# FRONT-UNIT-3_5.net
KiCad netlist of a schematic drawn in Altium Designer
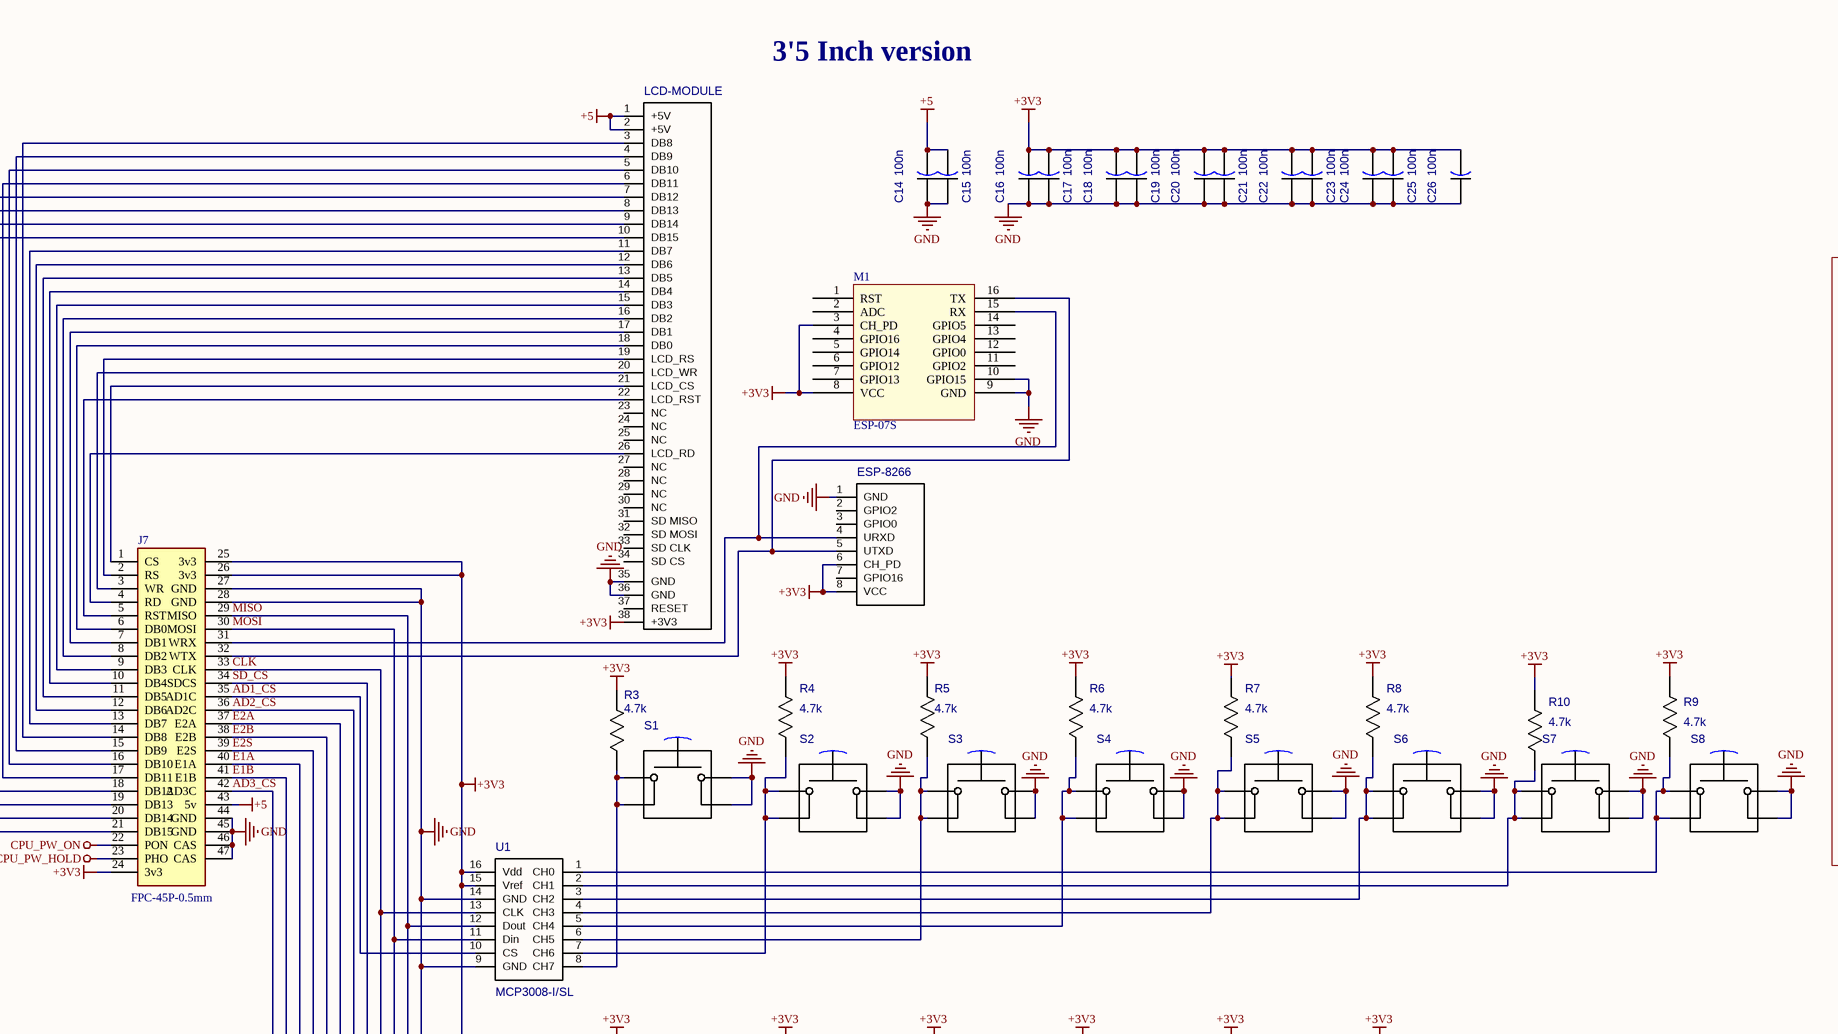
[diagram p0: FRONT-UNIT-3.5.SCHDOC, top left]
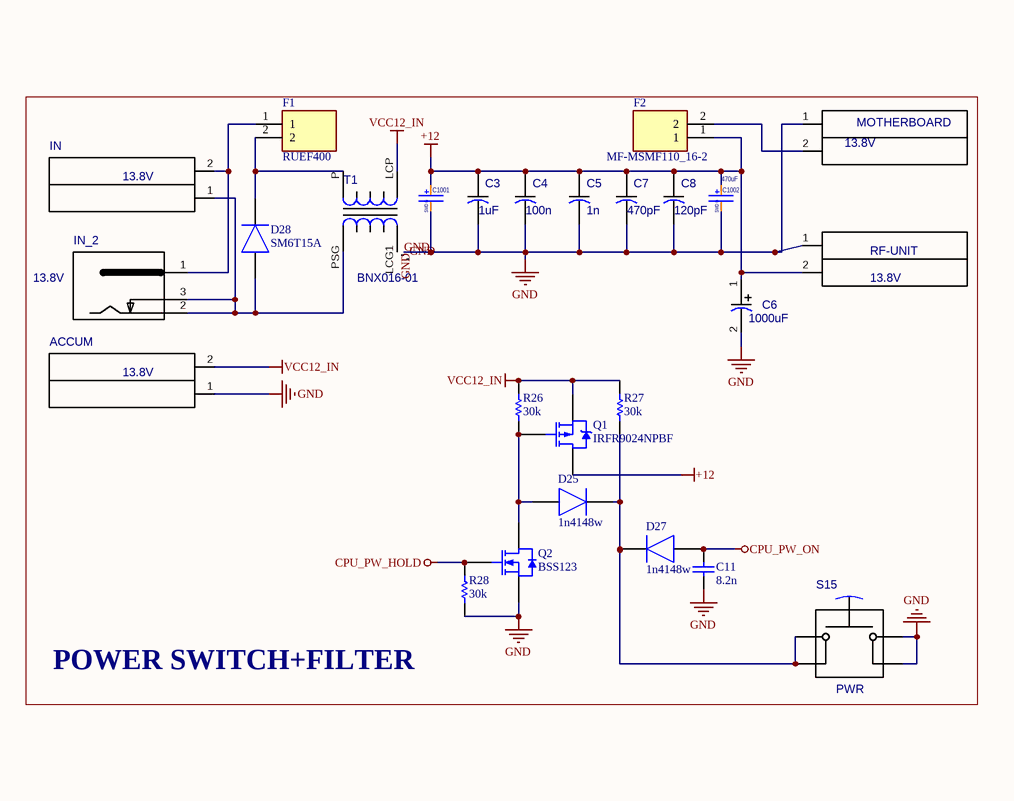
[diagram p1: FRONT-UNIT-3.5.SCHDOC, top right]
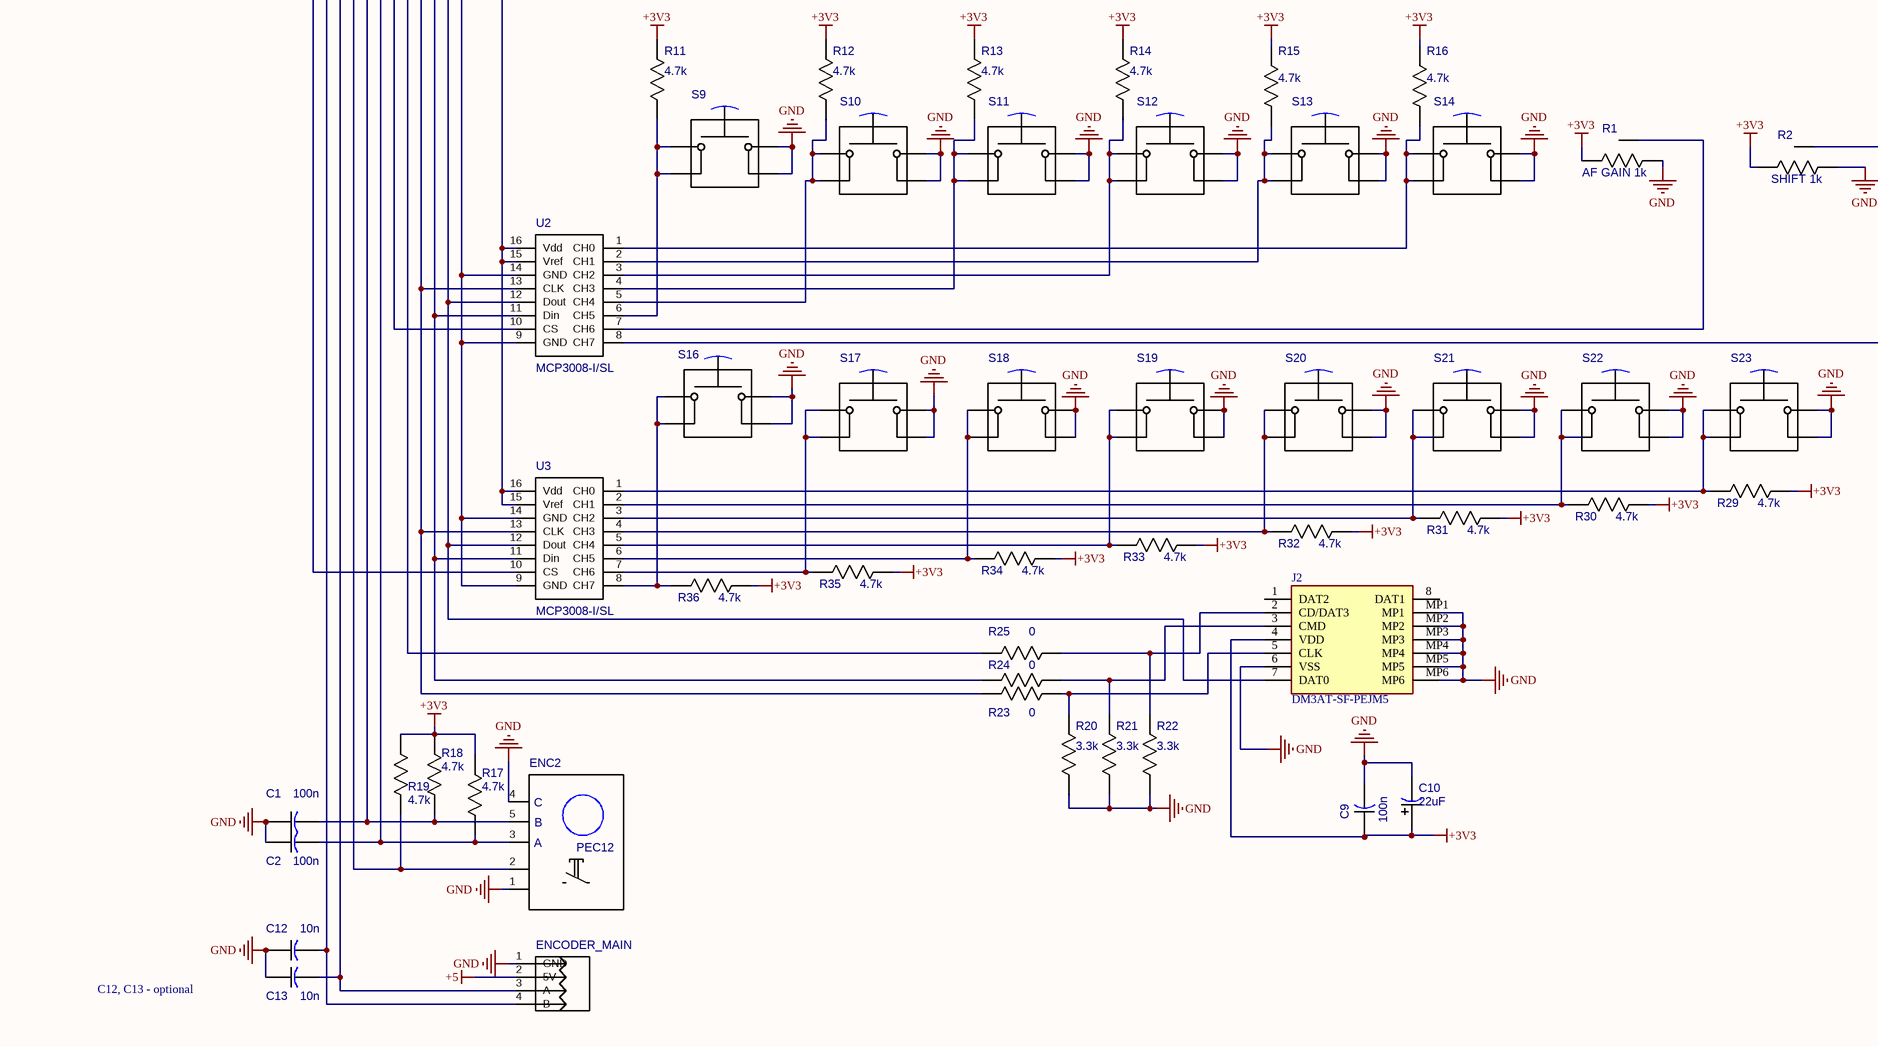
[diagram p2: FRONT-UNIT-3.5.SCHDOC, bottom left]
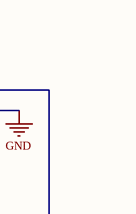
[diagram p3: FRONT-UNIT-3.5.SCHDOC, bottom right]

(export (version "E")
  (design (tool "Eeschema 10.0.6"))
  (components
    (comp (ref "ACCUM")
      (value "13.8V")
      (footprint "JX2")
      (description "JX2")
      (libsource (lib "*") (part "JX2"))
    )
    (comp (ref "C1")
      (value "100n")
      (footprint "CAP_0805")
      (description "CAP_0805")
      (libsource (lib "*") (part "CAP_0805"))
    )
    (comp (ref "C2")
      (value "100n")
      (footprint "CAP_0805")
      (description "CAP_0805")
      (libsource (lib "*") (part "CAP_0805"))
    )
    (comp (ref "C3")
      (value "1uF")
      (footprint "CAP_1206")
      (description "CAP_1206")
      (libsource (lib "*") (part "CAP_1206"))
    )
    (comp (ref "C4")
      (value "100n")
      (footprint "CAP_1206")
      (description "CAP_1206")
      (libsource (lib "*") (part "CAP_1206"))
    )
    (comp (ref "C5")
      (value "1n")
      (footprint "CAP_1206")
      (description "CAP_1206")
      (libsource (lib "*") (part "CAP_1206"))
    )
    (comp (ref "C6")
      (value "1000uF")
      (footprint "CAP250RP")
      (description "CAP250RP")
      (libsource (lib "FRONT-UNIT-3.5") (part "CAP250RP"))
    )
    (comp (ref "C7")
      (value "470pF")
      (footprint "CAP_1206")
      (description "CAP_1206")
      (libsource (lib "*") (part "CAP_1206"))
    )
    (comp (ref "C8")
      (value "120pF")
      (footprint "CAP_1206")
      (description "CAP_1206")
      (libsource (lib "*") (part "CAP_1206"))
    )
    (comp (ref "C9")
      (value "100n")
      (footprint "CAP_0805")
      (description "CAP_0805")
      (libsource (lib "*") (part "CAP_0805"))
    )
    (comp (ref "C10")
      (value "22uF")
      (footprint "EEEFC_sizeB")
      (description "EEEFC_sizeB")
      (libsource (lib "*") (part "EEEFC_sizeB"))
    )
    (comp (ref "C11")
      (value "8.2n")
      (footprint "CAPC2013X94X50LL20T25")
      (description "CAP_1206")
      (fields
        (field (name "MANUFACTURER") "AVX Interconnect / Elco")
        (field (name "PART NUMBER") "08055C822KAT2A")
      )
      (libsource (lib "Altium Content Vault") (part "CAP"))
    )
    (comp (ref "C12")
      (value "10n")
      (footprint "CAP_0805")
      (description "CAP_0805")
      (libsource (lib "*") (part "CAP_0805"))
    )
    (comp (ref "C13")
      (value "10n")
      (footprint "CAP_0805")
      (description "CAP_0805")
      (libsource (lib "*") (part "CAP_0805"))
    )
    (comp (ref "C14")
      (value "100n")
      (footprint "CAP_0805")
      (description "CAP_0805")
      (libsource (lib "*") (part "CAP_0805"))
    )
    (comp (ref "C15")
      (value "100n")
      (footprint "CAP_0805")
      (description "CAP_0805")
      (libsource (lib "*") (part "CAP_0805"))
    )
    (comp (ref "C16")
      (value "100n")
      (footprint "CAP_0805")
      (description "CAP_0805")
      (libsource (lib "*") (part "CAP_0805"))
    )
    (comp (ref "C17")
      (value "100n")
      (footprint "CAP_0805")
      (description "CAP_0805")
      (libsource (lib "*") (part "CAP_0805"))
    )
    (comp (ref "C18")
      (value "100n")
      (footprint "CAP_0805")
      (description "CAP_0805")
      (libsource (lib "*") (part "CAP_0805"))
    )
    (comp (ref "C19")
      (value "100n")
      (footprint "CAP_0805")
      (description "CAP_0805")
      (libsource (lib "*") (part "CAP_0805"))
    )
    (comp (ref "C20")
      (value "100n")
      (footprint "CAP_0805")
      (description "CAP_0805")
      (libsource (lib "*") (part "CAP_0805"))
    )
    (comp (ref "C21")
      (value "100n")
      (footprint "CAP_0805")
      (description "CAP_0805")
      (libsource (lib "*") (part "CAP_0805"))
    )
    (comp (ref "C22")
      (value "100n")
      (footprint "CAP_0805")
      (description "CAP_0805")
      (libsource (lib "*") (part "CAP_0805"))
    )
    (comp (ref "C23")
      (value "100n")
      (footprint "CAP_0805")
      (description "CAP_0805")
      (libsource (lib "*") (part "CAP_0805"))
    )
    (comp (ref "C24")
      (value "100n")
      (footprint "CAP_0805")
      (description "CAP_0805")
      (libsource (lib "*") (part "CAP_0805"))
    )
    (comp (ref "C25")
      (value "100n")
      (footprint "CAP_0805")
      (description "CAP_0805")
      (libsource (lib "*") (part "CAP_0805"))
    )
    (comp (ref "C26")
      (value "100n")
      (footprint "CAP_0805")
      (description "CAP_0805")
      (libsource (lib "*") (part "CAP_0805"))
    )
    (comp (ref "C1001")
      (value "470uF")
      (footprint "SMD-G-10X10.2")
      (description "10x7.7, 8.7, 10, 10.5, 12.5")
      (fields (field (name "PUBLISHER") "Catcatcat Electronics"))
      (libsource (lib "CapacitorElectrolytic") (part "_SMD-G-10"))
    )
    (comp (ref "C1002")
      (value "470uF")
      (footprint "SMD-G-10X10.2")
      (description "10x7.7, 8.7, 10, 10.5, 12.5")
      (fields (field (name "PUBLISHER") "Catcatcat Electronics"))
      (libsource (lib "CapacitorElectrolytic") (part "_SMD-G-10"))
    )
    (comp (ref "D25")
      (value "1n4148w")
      (footprint "SamacSys:SOD3716X135N")
      (description "Diode")
      (libsource (lib "*") (part "1n4148w"))
    )
    (comp (ref "D27")
      (value "1n4148w")
      (footprint "SamacSys:SOD3716X135N")
      (description "Diode")
      (libsource (lib "*") (part "1n4148w"))
    )
    (comp (ref "D28")
      (value "SM6T15A")
      (footprint "SamacSys:SMBJ36CATR")
      (description "Diode")
      (fields (field (name "MOUSER PART NUMBER") "511-SM6T15A") (field (name "RS PART NUMBER") "4864915P"))
      (libsource (lib "*") (part "SM6T15A"))
    )
    (comp (ref "ENC2") (value "PEC12") (footprint "PEC12") (libsource (lib "*") (part "PEC12")))
    (comp (ref "ENCODER_MAIN")
      (value "OPTICAL ENCODER")
      (footprint "644456-4")
      (libsource (lib "*") (part "644456-4"))
    )
    (comp (ref "ESP-8266")
      (value "ESP-01 ESP8266")
      (footprint "ESP-01 ESP8266")
      (libsource (lib "FRONT-UNIT") (part "ESP-01 ESP8266"))
    )
    (comp (ref "F1")
      (value "RUEF400")
      (footprint "SamacSys:RUEF400")
      (description "Fuse")
      (fields (field (name "MOUSER PART NUMBER") "650-RUEF400") (field (name "RS PART NUMBER") "5176837P"))
      (libsource (lib "*") (part "RUEF400"))
    )
    (comp (ref "F2")
      (value "MF-MSMF110_16-2")
      (footprint "SamacSys:FUSC4632X85N")
      (description "Fuse")
      (fields
        (field (name "MANUFACTURER_PART_NUMBER") "MF-MSMF110/16-2")
        (field (name "MOUSER PART NUMBER") "652-MF-MSMF110/16-2")
      )
      (libsource (lib "*") (part "MF-MSMF110_16-2"))
    )
    (comp (ref "IN") (value "13.8V") (footprint "JX2") (description "JX2") (libsource (lib "*") (part "JX2")))
    (comp (ref "IN_2")
      (value "13.8V")
      (footprint "PJ-050B")
      (description "PJ-050B")
      (libsource (lib "*") (part "PJ-050B"))
    )
    (comp (ref "J2")
      (value "DM3AT-SF-PEJM5")
      (footprint "FRONT-UNIT-71:DM3ATSFPEJM5")
      (description "Connector")
      (libsource (lib "FRONT-UNIT-71") (part "DM3AT-SF-PEJM5"))
    )
    (comp (ref "J7")
      (value "FPC-45P-0.5mm")
      (footprint "FRONT-UNIT-3.5:FH12S45S05SH60")
      (description "Connector")
      (fields
        (field (name "MANUFACTURER_PART_NUMBER") "FH12S-45S-0.5SH(55)")
        (field (name "MOUSER PART NUMBER") "798-FH12S-45S-05SH55")
      )
      (libsource (lib "*") (part "FH12S-45S-0.5SH_55_"))
    )
    (comp (ref "LCD-MODULE")
      (value "~")
      (footprint "LCD-MODULE-3.2-480-320")
      (description "LCD-MODULE_3'2_480х320")
      (libsource (lib "FRONT-UNIT-3.5") (part "LCD-MODULE_3'2_480х320"))
    )
    (comp (ref "M1")
      (value "ESP-07S")
      (footprint "modules:ESP-07S")
      (libsource (lib "modules") (part "ESP-07S"))
    )
    (comp (ref "MOTHERBOARD")
      (value "13.8V")
      (footprint "JX2")
      (description "JX2")
      (libsource (lib "*") (part "JX2"))
    )
    (comp (ref "Q1")
      (value "IRFR9024NPBF")
      (footprint "ONSC-DPAK-3-369C-01_V")
      (description "IRFR9024NPBF, Транзистор, Р-канал 55В 11А")
      (fields (field (name "MANUFACTURER") "On Semiconductor") (field (name "PARTNUMBER") "NTD2955G"))
      (libsource (lib "Altium Content Vault") (part "ONSC-PMOS-G1S3D4-3_B"))
    )
    (comp (ref "Q2")
      (value "BSS123")
      (footprint "FAIR-SOT23-3_V")
      (fields (field (name "MANUFACTURER") "Fairchild"))
      (libsource (lib "Altium Content Vault") (part "NEMOS-GSD-3"))
    )
    (comp (ref "R1")
      (value "AF GAIN 1k")
      (footprint "PTV09")
      (description "Adjustable Resistor PTV09")
      (fields (field (name "Comment") "ptv09a-4225f-b102"))
      (libsource (lib "*") (part "PTV09"))
    )
    (comp (ref "R2")
      (value "SHIFT 1k")
      (footprint "PTV09")
      (description "Adjustable Resistor PTV09")
      (fields (field (name "Comment") "ptv09a-4225f-b102"))
      (libsource (lib "*") (part "PTV09"))
    )
    (comp (ref "R3")
      (value "4.7k")
      (footprint "RES_0805")
      (description "RES_0805")
      (libsource (lib "*") (part "RES_0805"))
    )
    (comp (ref "R4")
      (value "4.7k")
      (footprint "RES_0805")
      (description "RES_0805")
      (libsource (lib "*") (part "RES_0805"))
    )
    (comp (ref "R5")
      (value "4.7k")
      (footprint "RES_0805")
      (description "RES_0805")
      (libsource (lib "*") (part "RES_0805"))
    )
    (comp (ref "R6")
      (value "4.7k")
      (footprint "RES_0805")
      (description "RES_0805")
      (libsource (lib "*") (part "RES_0805"))
    )
    (comp (ref "R7")
      (value "4.7k")
      (footprint "RES_0805")
      (description "RES_0805")
      (libsource (lib "*") (part "RES_0805"))
    )
    (comp (ref "R8")
      (value "4.7k")
      (footprint "RES_0805")
      (description "RES_0805")
      (libsource (lib "*") (part "RES_0805"))
    )
    (comp (ref "R9")
      (value "4.7k")
      (footprint "RES_0805")
      (description "RES_0805")
      (libsource (lib "*") (part "RES_0805"))
    )
    (comp (ref "R10")
      (value "4.7k")
      (footprint "RES_0805")
      (description "RES_0805")
      (libsource (lib "*") (part "RES_0805"))
    )
    (comp (ref "R11")
      (value "4.7k")
      (footprint "RES_0805")
      (description "RES_0805")
      (libsource (lib "*") (part "RES_0805"))
    )
    (comp (ref "R12")
      (value "4.7k")
      (footprint "RES_0805")
      (description "RES_0805")
      (libsource (lib "*") (part "RES_0805"))
    )
    (comp (ref "R13")
      (value "4.7k")
      (footprint "RES_0805")
      (description "RES_0805")
      (libsource (lib "*") (part "RES_0805"))
    )
    (comp (ref "R14")
      (value "4.7k")
      (footprint "RES_0805")
      (description "RES_0805")
      (libsource (lib "*") (part "RES_0805"))
    )
    (comp (ref "R15")
      (value "4.7k")
      (footprint "RES_0805")
      (description "RES_0805")
      (libsource (lib "*") (part "RES_0805"))
    )
    (comp (ref "R16")
      (value "4.7k")
      (footprint "RES_0805")
      (description "RES_0805")
      (libsource (lib "*") (part "RES_0805"))
    )
    (comp (ref "R17")
      (value "4.7k")
      (footprint "RES_0805")
      (description "RES_0805")
      (libsource (lib "*") (part "RES_0805"))
    )
    (comp (ref "R18")
      (value "4.7k")
      (footprint "RES_0805")
      (description "RES_0805")
      (libsource (lib "*") (part "RES_0805"))
    )
    (comp (ref "R19")
      (value "4.7k")
      (footprint "RES_0805")
      (description "RES_0805")
      (libsource (lib "*") (part "RES_0805"))
    )
    (comp (ref "R20")
      (value "3.3k")
      (footprint "RES_0805")
      (description "RES_0805")
      (libsource (lib "*") (part "RES_0805"))
    )
    (comp (ref "R21")
      (value "3.3k")
      (footprint "RES_0805")
      (description "RES_0805")
      (libsource (lib "*") (part "RES_0805"))
    )
    (comp (ref "R22")
      (value "3.3k")
      (footprint "RES_0805")
      (description "RES_0805")
      (libsource (lib "*") (part "RES_0805"))
    )
    (comp (ref "R23")
      (value "0")
      (footprint "RES_0805")
      (description "RES_0805")
      (libsource (lib "*") (part "RES_0805"))
    )
    (comp (ref "R24")
      (value "0")
      (footprint "RES_0805")
      (description "RES_0805")
      (libsource (lib "*") (part "RES_0805"))
    )
    (comp (ref "R25")
      (value "0")
      (footprint "RES_0805")
      (description "RES_0805")
      (libsource (lib "*") (part "RES_0805"))
    )
    (comp (ref "R26")
      (value "30k")
      (footprint "RESC2013X60X40NL20T25")
      (description "RES_0805")
      (fields (field (name "MANUFACTURER") "Panasonic") (field (name "PART NUMBER") "ERA-6AEB303V"))
      (libsource (lib "Altium Content Vault") (part "RES"))
    )
    (comp (ref "R27")
      (value "30k")
      (footprint "RESC2013X60X40NL20T25")
      (description "RES_0805")
      (fields (field (name "MANUFACTURER") "Panasonic") (field (name "PART NUMBER") "ERA-6AEB303V"))
      (libsource (lib "Altium Content Vault") (part "RES"))
    )
    (comp (ref "R28")
      (value "30k")
      (footprint "RESC2013X60X40NL20T25")
      (description "RES_0805")
      (fields (field (name "MANUFACTURER") "Panasonic") (field (name "PART NUMBER") "ERA-6AEB303V"))
      (libsource (lib "Altium Content Vault") (part "RES"))
    )
    (comp (ref "R29")
      (value "4.7k")
      (footprint "RES_0805")
      (description "RES_0805")
      (libsource (lib "*") (part "RES_0805"))
    )
    (comp (ref "R30")
      (value "4.7k")
      (footprint "RES_0805")
      (description "RES_0805")
      (libsource (lib "*") (part "RES_0805"))
    )
    (comp (ref "R31")
      (value "4.7k")
      (footprint "RES_0805")
      (description "RES_0805")
      (libsource (lib "*") (part "RES_0805"))
    )
    (comp (ref "R32")
      (value "4.7k")
      (footprint "RES_0805")
      (description "RES_0805")
      (libsource (lib "*") (part "RES_0805"))
    )
    (comp (ref "R33")
      (value "4.7k")
      (footprint "RES_0805")
      (description "RES_0805")
      (libsource (lib "*") (part "RES_0805"))
    )
    (comp (ref "R34")
      (value "4.7k")
      (footprint "RES_0805")
      (description "RES_0805")
      (libsource (lib "*") (part "RES_0805"))
    )
    (comp (ref "R35")
      (value "4.7k")
      (footprint "RES_0805")
      (description "RES_0805")
      (libsource (lib "*") (part "RES_0805"))
    )
    (comp (ref "R36")
      (value "4.7k")
      (footprint "RES_0805")
      (description "RES_0805")
      (libsource (lib "*") (part "RES_0805"))
    )
    (comp (ref "RF-UNIT")
      (value "13.8V")
      (footprint "JX2")
      (description "JX2")
      (libsource (lib "*") (part "JX2"))
    )
    (comp (ref "S1")
      (value "PTS645SK50LFS")
      (footprint "PTS645SK50LFS")
      (fields (field (name "LCSC PART #") "test"))
      (libsource (lib "*") (part "PTS645SK50LFS"))
    )
    (comp (ref "S2")
      (value "PTS645SK50LFS")
      (footprint "PTS645SK50LFS")
      (libsource (lib "*") (part "PTS645SK50LFS"))
    )
    (comp (ref "S3")
      (value "PTS645SK50LFS")
      (footprint "PTS645SK50LFS")
      (libsource (lib "*") (part "PTS645SK50LFS"))
    )
    (comp (ref "S4")
      (value "PTS645SK50LFS")
      (footprint "PTS645SK50LFS")
      (libsource (lib "*") (part "PTS645SK50LFS"))
    )
    (comp (ref "S5")
      (value "PTS645SK50LFS")
      (footprint "PTS645SK50LFS")
      (libsource (lib "*") (part "PTS645SK50LFS"))
    )
    (comp (ref "S6")
      (value "PTS645SK50LFS")
      (footprint "PTS645SK50LFS")
      (libsource (lib "*") (part "PTS645SK50LFS"))
    )
    (comp (ref "S7")
      (value "PTS645SK50LFS")
      (footprint "PTS645SK50LFS")
      (libsource (lib "*") (part "PTS645SK50LFS"))
    )
    (comp (ref "S8")
      (value "PTS645SK50LFS")
      (footprint "PTS645SK50LFS")
      (libsource (lib "*") (part "PTS645SK50LFS"))
    )
    (comp (ref "S9")
      (value "PTS645SK50LFS")
      (footprint "PTS645SK50LFS")
      (libsource (lib "*") (part "PTS645SK50LFS"))
    )
    (comp (ref "S10")
      (value "PTS645SK50LFS")
      (footprint "PTS645SK50LFS")
      (libsource (lib "*") (part "PTS645SK50LFS"))
    )
    (comp (ref "S11")
      (value "PTS645SK50LFS")
      (footprint "PTS645SK50LFS")
      (libsource (lib "*") (part "PTS645SK50LFS"))
    )
    (comp (ref "S12")
      (value "PTS645SK50LFS")
      (footprint "PTS645SK50LFS")
      (libsource (lib "*") (part "PTS645SK50LFS"))
    )
    (comp (ref "S13")
      (value "PTS645SK50LFS")
      (footprint "PTS645SK50LFS")
      (libsource (lib "*") (part "PTS645SK50LFS"))
    )
    (comp (ref "S14")
      (value "PTS645SK50LFS")
      (footprint "PTS645SK50LFS")
      (libsource (lib "*") (part "PTS645SK50LFS"))
    )
    (comp (ref "S15")
      (value "PWR")
      (footprint "PTS645SK50LFS")
      (description "PTS645SK50LFS")
      (libsource (lib "*") (part "PTS645SK50LFS"))
    )
    (comp (ref "S16")
      (value "PTS645SK50LFS")
      (footprint "PTS645SK50LFS")
      (libsource (lib "*") (part "PTS645SK50LFS"))
    )
    (comp (ref "S17")
      (value "PTS645SK50LFS")
      (footprint "PTS645SK50LFS")
      (libsource (lib "*") (part "PTS645SK50LFS"))
    )
    (comp (ref "S18")
      (value "PTS645SK50LFS")
      (footprint "PTS645SK50LFS")
      (libsource (lib "*") (part "PTS645SK50LFS"))
    )
    (comp (ref "S19")
      (value "PTS645SK50LFS")
      (footprint "PTS645SK50LFS")
      (libsource (lib "*") (part "PTS645SK50LFS"))
    )
    (comp (ref "S20")
      (value "PTS645SK50LFS")
      (footprint "PTS645SK50LFS")
      (libsource (lib "*") (part "PTS645SK50LFS"))
    )
    (comp (ref "S21")
      (value "PTS645SK50LFS")
      (footprint "PTS645SK50LFS")
      (libsource (lib "*") (part "PTS645SK50LFS"))
    )
    (comp (ref "S22")
      (value "PTS645SK50LFS")
      (footprint "PTS645SK50LFS")
      (libsource (lib "*") (part "PTS645SK50LFS"))
    )
    (comp (ref "S23")
      (value "PTS645SK50LFS")
      (footprint "PTS645SK50LFS")
      (libsource (lib "*") (part "PTS645SK50LFS"))
    )
    (comp (ref "T1")
      (value "BNX016-01")
      (footprint "TRANSF_ICORE")
      (libsource (lib "*") (part "TRANSF_ICORE"))
    )
    (comp (ref "U1")
      (value "MCP3008-I/SL")
      (footprint "MCP3008-I/SL")
      (libsource (lib "*") (part "MCP3008-I/SL"))
    )
    (comp (ref "U2")
      (value "MCP3008-I/SL")
      (footprint "MCP3008-I/SL")
      (libsource (lib "*") (part "MCP3008-I/SL"))
    )
    (comp (ref "U3")
      (value "MCP3008-I/SL")
      (footprint "MCP3008-I/SL")
      (libsource (lib "*") (part "MCP3008-I/SL"))
    )
  )
  (nets
    (net (code "1") (name "+3V3") (class "Default")
      (node (ref "C10") (pin "1") (pinfunction "PLUS_1") (pintype "passive"))
      (node (ref "C16") (pin "2") (pinfunction "2_2") (pintype "passive"))
      (node (ref "C17") (pin "2") (pinfunction "2_2") (pintype "passive"))
      (node (ref "C18") (pin "2") (pinfunction "2_2") (pintype "passive"))
      (node (ref "C19") (pin "2") (pinfunction "2_2") (pintype "passive"))
      (node (ref "C20") (pin "2") (pinfunction "2_2") (pintype "passive"))
      (node (ref "C21") (pin "2") (pinfunction "2_2") (pintype "passive"))
      (node (ref "C22") (pin "2") (pinfunction "2_2") (pintype "passive"))
      (node (ref "C23") (pin "2") (pinfunction "2_2") (pintype "passive"))
      (node (ref "C24") (pin "2") (pinfunction "2_2") (pintype "passive"))
      (node (ref "C25") (pin "2") (pinfunction "2_2") (pintype "passive"))
      (node (ref "C26") (pin "2") (pinfunction "2_2") (pintype "passive"))
      (node (ref "C9") (pin "1") (pinfunction "1_1") (pintype "passive"))
      (node (ref "ESP-8266") (pin "6") (pinfunction "CH_PD_6") (pintype "passive"))
      (node (ref "ESP-8266") (pin "8") (pinfunction "VCC_8") (pintype "passive"))
      (node (ref "J2") (pin "4") (pinfunction "VDD_4") (pintype "passive"))
      (node (ref "J7") (pin "24") (pinfunction "3v3_24") (pintype "passive"))
      (node (ref "J7") (pin "25") (pinfunction "3v3_25") (pintype "passive"))
      (node (ref "J7") (pin "26") (pinfunction "3v3_26") (pintype "passive"))
      (node (ref "LCD-MODULE") (pin "38") (pinfunction "+3V3_38") (pintype "passive"))
      (node (ref "M1") (pin "3") (pinfunction "CH_PD_3") (pintype "passive"))
      (node (ref "M1") (pin "8") (pinfunction "VCC_8") (pintype "passive"))
      (node (ref "R1") (pin "1") (pinfunction "CW_1") (pintype "passive"))
      (node (ref "R10") (pin "2") (pinfunction "2_2") (pintype "passive"))
      (node (ref "R11") (pin "2") (pinfunction "2_2") (pintype "passive"))
      (node (ref "R12") (pin "2") (pinfunction "2_2") (pintype "passive"))
      (node (ref "R13") (pin "2") (pinfunction "2_2") (pintype "passive"))
      (node (ref "R14") (pin "2") (pinfunction "2_2") (pintype "passive"))
      (node (ref "R15") (pin "2") (pinfunction "2_2") (pintype "passive"))
      (node (ref "R16") (pin "2") (pinfunction "2_2") (pintype "passive"))
      (node (ref "R17") (pin "2") (pinfunction "2_2") (pintype "passive"))
      (node (ref "R18") (pin "2") (pinfunction "2_2") (pintype "passive"))
      (node (ref "R19") (pin "2") (pinfunction "2_2") (pintype "passive"))
      (node (ref "R2") (pin "1") (pinfunction "CW_1") (pintype "passive"))
      (node (ref "R29") (pin "2") (pinfunction "2_2") (pintype "passive"))
      (node (ref "R3") (pin "2") (pinfunction "2_2") (pintype "passive"))
      (node (ref "R30") (pin "2") (pinfunction "2_2") (pintype "passive"))
      (node (ref "R31") (pin "2") (pinfunction "2_2") (pintype "passive"))
      (node (ref "R32") (pin "2") (pinfunction "2_2") (pintype "passive"))
      (node (ref "R33") (pin "2") (pinfunction "2_2") (pintype "passive"))
      (node (ref "R34") (pin "2") (pinfunction "2_2") (pintype "passive"))
      (node (ref "R35") (pin "2") (pinfunction "2_2") (pintype "passive"))
      (node (ref "R36") (pin "2") (pinfunction "2_2") (pintype "passive"))
      (node (ref "R4") (pin "2") (pinfunction "2_2") (pintype "passive"))
      (node (ref "R5") (pin "2") (pinfunction "2_2") (pintype "passive"))
      (node (ref "R6") (pin "2") (pinfunction "2_2") (pintype "passive"))
      (node (ref "R7") (pin "2") (pinfunction "2_2") (pintype "passive"))
      (node (ref "R8") (pin "2") (pinfunction "2_2") (pintype "passive"))
      (node (ref "R9") (pin "2") (pinfunction "2_2") (pintype "passive"))
      (node (ref "U1") (pin "15") (pinfunction "Vref_15") (pintype "passive"))
      (node (ref "U1") (pin "16") (pinfunction "Vdd_16") (pintype "passive"))
      (node (ref "U2") (pin "15") (pinfunction "Vref_15") (pintype "passive"))
      (node (ref "U2") (pin "16") (pinfunction "Vdd_16") (pintype "passive"))
      (node (ref "U3") (pin "15") (pinfunction "Vref_15") (pintype "passive"))
      (node (ref "U3") (pin "16") (pinfunction "Vdd_16") (pintype "passive"))
    )
    (net (code "2") (name "+5") (class "Default")
      (node (ref "C14") (pin "2") (pinfunction "2_2") (pintype "passive"))
      (node (ref "C15") (pin "2") (pinfunction "2_2") (pintype "passive"))
      (node (ref "ENCODER_MAIN") (pin "2") (pinfunction "5V_2") (pintype "passive"))
      (node (ref "J7") (pin "43") (pinfunction "5v_43") (pintype "passive"))
      (node (ref "LCD-MODULE") (pin "1") (pinfunction "+5V_1") (pintype "passive"))
      (node (ref "LCD-MODULE") (pin "2") (pinfunction "+5V_2") (pintype "passive"))
    )
    (net (code "3") (name "+12") (class "Default")
      (node (ref "C1001") (pin "1") (pinfunction "1_1") (pintype "passive"))
      (node (ref "C1002") (pin "1") (pinfunction "1_1") (pintype "passive"))
      (node (ref "C3") (pin "1") (pinfunction "1_1") (pintype "passive"))
      (node (ref "C4") (pin "1") (pinfunction "1_1") (pintype "passive"))
      (node (ref "C5") (pin "1") (pinfunction "1_1") (pintype "passive"))
      (node (ref "C6") (pin "1") (pinfunction "PLUS_1") (pintype "passive"))
      (node (ref "C7") (pin "1") (pinfunction "1_1") (pintype "passive"))
      (node (ref "C8") (pin "1") (pinfunction "1_1") (pintype "passive"))
      (node (ref "F2") (pin "1") (pinfunction "1_1") (pintype "passive"))
      (node (ref "Q1") (pin "4") (pinfunction "D_4") (pintype "passive"))
      (node (ref "RF-UNIT") (pin "2") (pinfunction "1_2") (pintype "passive"))
    )
    (net (code "4") (name "/AD1_CS") (class "Default")
      (node (ref "J7") (pin "35") (pinfunction "AD1C_35") (pintype "passive"))
      (node (ref "U1") (pin "10") (pinfunction "CS_10") (pintype "passive"))
    )
    (net (code "5") (name "/AD2_CS") (class "Default")
      (node (ref "J7") (pin "36") (pinfunction "AD2C_36") (pintype "passive"))
      (node (ref "U2") (pin "10") (pinfunction "CS_10") (pintype "passive"))
    )
    (net (code "6") (name "/AD3_CS") (class "Default")
      (node (ref "J7") (pin "42") (pinfunction "AD3C_42") (pintype "passive"))
      (node (ref "U3") (pin "10") (pinfunction "CS_10") (pintype "passive"))
    )
    (net (code "7") (name "/CLK") (class "Default")
      (node (ref "J7") (pin "33") (pinfunction "CLK_33") (pintype "passive"))
      (node (ref "R23") (pin "2") (pinfunction "2_2") (pintype "passive"))
      (node (ref "U1") (pin "13") (pinfunction "CLK_13") (pintype "passive"))
      (node (ref "U2") (pin "13") (pinfunction "CLK_13") (pintype "passive"))
      (node (ref "U3") (pin "13") (pinfunction "CLK_13") (pintype "passive"))
    )
    (net (code "8") (name "/E1A") (class "Default")
      (node (ref "C13") (pin "2") (pinfunction "2_2") (pintype "passive"))
      (node (ref "ENCODER_MAIN") (pin "3") (pinfunction "A_3") (pintype "passive"))
      (node (ref "J7") (pin "40") (pinfunction "E1A_40") (pintype "passive"))
    )
    (net (code "9") (name "/E1B") (class "Default")
      (node (ref "C12") (pin "2") (pinfunction "2_2") (pintype "passive"))
      (node (ref "ENCODER_MAIN") (pin "4") (pinfunction "B_4") (pintype "passive"))
      (node (ref "J7") (pin "41") (pinfunction "E1B_41") (pintype "passive"))
    )
    (net (code "10") (name "/E2A") (class "Default")
      (node (ref "C2") (pin "2") (pinfunction "2_2") (pintype "passive"))
      (node (ref "ENC2") (pin "3") (pinfunction "A_3") (pintype "passive"))
      (node (ref "J7") (pin "37") (pinfunction "E2A_37") (pintype "passive"))
      (node (ref "R17") (pin "1") (pinfunction "1_1") (pintype "passive"))
    )
    (net (code "11") (name "/E2B") (class "Default")
      (node (ref "C1") (pin "2") (pinfunction "2_2") (pintype "passive"))
      (node (ref "ENC2") (pin "5") (pinfunction "B_5") (pintype "passive"))
      (node (ref "J7") (pin "38") (pinfunction "E2B_38") (pintype "passive"))
      (node (ref "R18") (pin "1") (pinfunction "1_1") (pintype "passive"))
    )
    (net (code "12") (name "/E2S") (class "Default")
      (node (ref "ENC2") (pin "2") (pinfunction "2_2") (pintype "passive"))
      (node (ref "J7") (pin "39") (pinfunction "E2S_39") (pintype "passive"))
      (node (ref "R19") (pin "1") (pinfunction "1_1") (pintype "passive"))
    )
    (net (code "13") (name "/MISO") (class "Default")
      (node (ref "J2") (pin "7") (pinfunction "DAT0_7") (pintype "passive"))
      (node (ref "J7") (pin "29") (pinfunction "MISO_29") (pintype "passive"))
      (node (ref "U1") (pin "12") (pinfunction "Dout_12") (pintype "passive"))
      (node (ref "U2") (pin "12") (pinfunction "Dout_12") (pintype "passive"))
      (node (ref "U3") (pin "12") (pinfunction "Dout_12") (pintype "passive"))
    )
    (net (code "14") (name "/MOSI") (class "Default")
      (node (ref "J7") (pin "30") (pinfunction "MOSI_30") (pintype "passive"))
      (node (ref "R24") (pin "2") (pinfunction "2_2") (pintype "passive"))
      (node (ref "U1") (pin "11") (pinfunction "Din_11") (pintype "passive"))
      (node (ref "U2") (pin "11") (pinfunction "Din_11") (pintype "passive"))
      (node (ref "U3") (pin "11") (pinfunction "Din_11") (pintype "passive"))
    )
    (net (code "15") (name "/SD_CS") (class "Default")
      (node (ref "J7") (pin "34") (pinfunction "SDCS_34") (pintype "passive"))
      (node (ref "R25") (pin "2") (pinfunction "2_2") (pintype "passive"))
    )
    (net (code "16") (name "CPU_PW_HOLD") (class "Default")
      (node (ref "J7") (pin "23") (pinfunction "PHO_23") (pintype "passive"))
      (node (ref "Q2") (pin "1") (pinfunction "G_1") (pintype "passive"))
      (node (ref "R28") (pin "2") (pinfunction "2_2") (pintype "passive"))
    )
    (net (code "17") (name "CPU_PW_ON") (class "Default")
      (node (ref "C11") (pin "2") (pinfunction "2_2") (pintype "passive"))
      (node (ref "D27") (pin "2") (pinfunction "A_2") (pintype "passive"))
      (node (ref "J7") (pin "22") (pinfunction "PON_22") (pintype "passive"))
    )
    (net (code "18") (name "GND") (class "Default")
      (node (ref "ACCUM") (pin "1") (pinfunction "2_1") (pintype "passive"))
      (node (ref "C1") (pin "1") (pinfunction "1_1") (pintype "passive"))
      (node (ref "C10") (pin "2") (pinfunction "MINUS_2") (pintype "passive"))
      (node (ref "C1001") (pin "2") (pinfunction "2_2") (pintype "passive"))
      (node (ref "C1002") (pin "2") (pinfunction "2_2") (pintype "passive"))
      (node (ref "C11") (pin "1") (pinfunction "1_1") (pintype "passive"))
      (node (ref "C12") (pin "1") (pinfunction "1_1") (pintype "passive"))
      (node (ref "C13") (pin "1") (pinfunction "1_1") (pintype "passive"))
      (node (ref "C14") (pin "1") (pinfunction "1_1") (pintype "passive"))
      (node (ref "C15") (pin "1") (pinfunction "1_1") (pintype "passive"))
      (node (ref "C16") (pin "1") (pinfunction "1_1") (pintype "passive"))
      (node (ref "C17") (pin "1") (pinfunction "1_1") (pintype "passive"))
      (node (ref "C18") (pin "1") (pinfunction "1_1") (pintype "passive"))
      (node (ref "C19") (pin "1") (pinfunction "1_1") (pintype "passive"))
      (node (ref "C2") (pin "1") (pinfunction "1_1") (pintype "passive"))
      (node (ref "C20") (pin "1") (pinfunction "1_1") (pintype "passive"))
      (node (ref "C21") (pin "1") (pinfunction "1_1") (pintype "passive"))
      (node (ref "C22") (pin "1") (pinfunction "1_1") (pintype "passive"))
      (node (ref "C23") (pin "1") (pinfunction "1_1") (pintype "passive"))
      (node (ref "C24") (pin "1") (pinfunction "1_1") (pintype "passive"))
      (node (ref "C25") (pin "1") (pinfunction "1_1") (pintype "passive"))
      (node (ref "C26") (pin "1") (pinfunction "1_1") (pintype "passive"))
      (node (ref "C3") (pin "2") (pinfunction "2_2") (pintype "passive"))
      (node (ref "C4") (pin "2") (pinfunction "2_2") (pintype "passive"))
      (node (ref "C5") (pin "2") (pinfunction "2_2") (pintype "passive"))
      (node (ref "C6") (pin "2") (pinfunction "MINUS_2") (pintype "passive"))
      (node (ref "C7") (pin "2") (pinfunction "2_2") (pintype "passive"))
      (node (ref "C8") (pin "2") (pinfunction "2_2") (pintype "passive"))
      (node (ref "C9") (pin "2") (pinfunction "2_2") (pintype "passive"))
      (node (ref "ENC2") (pin "1") (pinfunction "1_1") (pintype "passive"))
      (node (ref "ENC2") (pin "4") (pinfunction "C_4") (pintype "passive"))
      (node (ref "ENCODER_MAIN") (pin "1") (pinfunction "GND_1") (pintype "passive"))
      (node (ref "ESP-8266") (pin "1") (pinfunction "GND_1") (pintype "passive"))
      (node (ref "J2") (pin "6") (pinfunction "VSS_6") (pintype "passive"))
      (node (ref "J2") (pin "MP1") (pinfunction "MP1_MP1") (pintype "passive"))
      (node (ref "J2") (pin "MP2") (pinfunction "MP2_MP2") (pintype "passive"))
      (node (ref "J2") (pin "MP3") (pinfunction "MP3_MP3") (pintype "passive"))
      (node (ref "J2") (pin "MP4") (pinfunction "MP4_MP4") (pintype "passive"))
      (node (ref "J2") (pin "MP5") (pinfunction "MP5_MP5") (pintype "passive"))
      (node (ref "J2") (pin "MP6") (pinfunction "MP6_MP6") (pintype "passive"))
      (node (ref "J7") (pin "27") (pinfunction "GND_27") (pintype "passive"))
      (node (ref "J7") (pin "28") (pinfunction "GND_28") (pintype "passive"))
      (node (ref "J7") (pin "44") (pinfunction "GND_44") (pintype "passive"))
      (node (ref "J7") (pin "45") (pinfunction "GND_45") (pintype "passive"))
      (node (ref "J7") (pin "46") (pinfunction "CAS_46") (pintype "passive"))
      (node (ref "J7") (pin "47") (pinfunction "CAS_47") (pintype "passive"))
      (node (ref "LCD-MODULE") (pin "35") (pinfunction "GND_35") (pintype "passive"))
      (node (ref "LCD-MODULE") (pin "36") (pinfunction "GND_36") (pintype "passive"))
      (node (ref "M1") (pin "10") (pinfunction "GPIO15_10") (pintype "passive"))
      (node (ref "M1") (pin "9") (pinfunction "GND_9") (pintype "passive"))
      (node (ref "MOTHERBOARD") (pin "1") (pinfunction "2_1") (pintype "passive"))
      (node (ref "Q2") (pin "2") (pinfunction "S_2") (pintype "passive"))
      (node (ref "R1") (pin "3") (pinfunction "CCW_3") (pintype "passive"))
      (node (ref "R2") (pin "3") (pinfunction "CCW_3") (pintype "passive"))
      (node (ref "R20") (pin "1") (pinfunction "1_1") (pintype "passive"))
      (node (ref "R21") (pin "1") (pinfunction "1_1") (pintype "passive"))
      (node (ref "R22") (pin "1") (pinfunction "1_1") (pintype "passive"))
      (node (ref "R28") (pin "1") (pinfunction "1_1") (pintype "passive"))
      (node (ref "RF-UNIT") (pin "1") (pinfunction "2_1") (pintype "passive"))
      (node (ref "S1") (pin "3") (pinfunction "B_3") (pintype "passive"))
      (node (ref "S1") (pin "4") (pinfunction "B_4") (pintype "passive"))
      (node (ref "S10") (pin "3") (pinfunction "B_3") (pintype "passive"))
      (node (ref "S10") (pin "4") (pinfunction "B_4") (pintype "passive"))
      (node (ref "S11") (pin "3") (pinfunction "B_3") (pintype "passive"))
      (node (ref "S11") (pin "4") (pinfunction "B_4") (pintype "passive"))
      (node (ref "S12") (pin "3") (pinfunction "B_3") (pintype "passive"))
      (node (ref "S12") (pin "4") (pinfunction "B_4") (pintype "passive"))
      (node (ref "S13") (pin "3") (pinfunction "B_3") (pintype "passive"))
      (node (ref "S13") (pin "4") (pinfunction "B_4") (pintype "passive"))
      (node (ref "S14") (pin "3") (pinfunction "B_3") (pintype "passive"))
      (node (ref "S14") (pin "4") (pinfunction "B_4") (pintype "passive"))
      (node (ref "S15") (pin "3") (pinfunction "B_3") (pintype "passive"))
      (node (ref "S15") (pin "4") (pinfunction "B_4") (pintype "passive"))
      (node (ref "S16") (pin "3") (pinfunction "B_3") (pintype "passive"))
      (node (ref "S16") (pin "4") (pinfunction "B_4") (pintype "passive"))
      (node (ref "S17") (pin "3") (pinfunction "B_3") (pintype "passive"))
      (node (ref "S17") (pin "4") (pinfunction "B_4") (pintype "passive"))
      (node (ref "S18") (pin "3") (pinfunction "B_3") (pintype "passive"))
      (node (ref "S18") (pin "4") (pinfunction "B_4") (pintype "passive"))
      (node (ref "S19") (pin "3") (pinfunction "B_3") (pintype "passive"))
      (node (ref "S19") (pin "4") (pinfunction "B_4") (pintype "passive"))
      (node (ref "S2") (pin "3") (pinfunction "B_3") (pintype "passive"))
      (node (ref "S2") (pin "4") (pinfunction "B_4") (pintype "passive"))
      (node (ref "S20") (pin "3") (pinfunction "B_3") (pintype "passive"))
      (node (ref "S20") (pin "4") (pinfunction "B_4") (pintype "passive"))
      (node (ref "S21") (pin "3") (pinfunction "B_3") (pintype "passive"))
      (node (ref "S21") (pin "4") (pinfunction "B_4") (pintype "passive"))
      (node (ref "S22") (pin "3") (pinfunction "B_3") (pintype "passive"))
      (node (ref "S22") (pin "4") (pinfunction "B_4") (pintype "passive"))
      (node (ref "S23") (pin "3") (pinfunction "B_3") (pintype "passive"))
      (node (ref "S23") (pin "4") (pinfunction "B_4") (pintype "passive"))
      (node (ref "S3") (pin "3") (pinfunction "B_3") (pintype "passive"))
      (node (ref "S3") (pin "4") (pinfunction "B_4") (pintype "passive"))
      (node (ref "S4") (pin "3") (pinfunction "B_3") (pintype "passive"))
      (node (ref "S4") (pin "4") (pinfunction "B_4") (pintype "passive"))
      (node (ref "S5") (pin "3") (pinfunction "B_3") (pintype "passive"))
      (node (ref "S5") (pin "4") (pinfunction "B_4") (pintype "passive"))
      (node (ref "S6") (pin "3") (pinfunction "B_3") (pintype "passive"))
      (node (ref "S6") (pin "4") (pinfunction "B_4") (pintype "passive"))
      (node (ref "S7") (pin "3") (pinfunction "B_3") (pintype "passive"))
      (node (ref "S7") (pin "4") (pinfunction "B_4") (pintype "passive"))
      (node (ref "S8") (pin "3") (pinfunction "B_3") (pintype "passive"))
      (node (ref "S8") (pin "4") (pinfunction "B_4") (pintype "passive"))
      (node (ref "S9") (pin "3") (pinfunction "B_3") (pintype "passive"))
      (node (ref "S9") (pin "4") (pinfunction "B_4") (pintype "passive"))
      (node (ref "T1") (pin "LCG1") (pinfunction "S2_LCG1") (pintype "passive"))
      (node (ref "T1") (pin "LCG2") (pinfunction "0_LCG2") (pintype "passive"))
      (node (ref "T1") (pin "LCG3") (pinfunction "0_LCG3") (pintype "passive"))
      (node (ref "U1") (pin "14") (pinfunction "GND_14") (pintype "passive"))
      (node (ref "U1") (pin "9") (pinfunction "GND_9") (pintype "passive"))
      (node (ref "U2") (pin "14") (pinfunction "GND_14") (pintype "passive"))
      (node (ref "U2") (pin "9") (pinfunction "GND_9") (pintype "passive"))
      (node (ref "U3") (pin "14") (pinfunction "GND_14") (pintype "passive"))
      (node (ref "U3") (pin "9") (pinfunction "GND_9") (pintype "passive"))
    )
    (net (code "19") (name "Net-(D25-A)") (class "Default")
      (node (ref "D25") (pin "2") (pinfunction "A_2") (pintype "passive"))
      (node (ref "Q1") (pin "1") (pinfunction "G_1") (pintype "passive"))
      (node (ref "Q2") (pin "3") (pinfunction "D_3") (pintype "passive"))
      (node (ref "R26") (pin "1") (pinfunction "1_1") (pintype "passive"))
    )
    (net (code "20") (name "Net-(D25-K)") (class "Default")
      (node (ref "D25") (pin "1") (pinfunction "K_1") (pintype "passive"))
      (node (ref "D27") (pin "1") (pinfunction "K_1") (pintype "passive"))
      (node (ref "R27") (pin "1") (pinfunction "1_1") (pintype "passive"))
      (node (ref "S15") (pin "1") (pinfunction "A_1") (pintype "passive"))
      (node (ref "S15") (pin "2") (pinfunction "A_2") (pintype "passive"))
    )
    (net (code "21") (name "Net-(D28-A)") (class "Default")
      (node (ref "D28") (pin "2") (pinfunction "A_2") (pintype "passive"))
      (node (ref "IN") (pin "1") (pinfunction "2_1") (pintype "passive"))
      (node (ref "IN_2") (pin "2") (pinfunction "2_2") (pintype "passive"))
      (node (ref "IN_2") (pin "3") (pinfunction "3_3") (pintype "passive"))
      (node (ref "T1") (pin "PSG") (pinfunction "S1_PSG") (pintype "passive"))
    )
    (net (code "22") (name "Net-(D28-K)") (class "Default")
      (node (ref "D28") (pin "1") (pinfunction "K_1") (pintype "passive"))
      (node (ref "F1") (pin "2") (pinfunction "2_2") (pintype "passive"))
      (node (ref "T1") (pin "P") (pinfunction "P1_P") (pintype "passive"))
    )
    (net (code "23") (name "Net-(ESP-8266-URXD)") (class "Default")
      (node (ref "ESP-8266") (pin "4") (pinfunction "URXD_4") (pintype "passive"))
      (node (ref "J7") (pin "31") (pinfunction "WRX_31") (pintype "passive"))
      (node (ref "M1") (pin "15") (pinfunction "RX_15") (pintype "passive"))
    )
    (net (code "24") (name "Net-(ESP-8266-UTXD)") (class "Default")
      (node (ref "ESP-8266") (pin "5") (pinfunction "UTXD_5") (pintype "passive"))
      (node (ref "J7") (pin "32") (pinfunction "WTX_32") (pintype "passive"))
      (node (ref "M1") (pin "16") (pinfunction "TX_16") (pintype "passive"))
    )
    (net (code "25") (name "Net-(IN-1)") (class "Default")
      (node (ref "F1") (pin "1") (pinfunction "1_1") (pintype "passive"))
      (node (ref "IN") (pin "2") (pinfunction "1_2") (pintype "passive"))
      (node (ref "IN_2") (pin "1") (pinfunction "1_1") (pintype "passive"))
    )
    (net (code "26") (name "Net-(J2-CD{slash}DAT3)") (class "Default")
      (node (ref "J2") (pin "2") (pinfunction "CD/DAT3_2") (pintype "passive"))
      (node (ref "R22") (pin "2") (pinfunction "2_2") (pintype "passive"))
      (node (ref "R25") (pin "1") (pinfunction "1_1") (pintype "passive"))
    )
    (net (code "27") (name "Net-(J2-CLK)") (class "Default")
      (node (ref "J2") (pin "5") (pinfunction "CLK_5") (pintype "passive"))
      (node (ref "R20") (pin "2") (pinfunction "2_2") (pintype "passive"))
      (node (ref "R23") (pin "1") (pinfunction "1_1") (pintype "passive"))
    )
    (net (code "28") (name "Net-(J2-CMD)") (class "Default")
      (node (ref "J2") (pin "3") (pinfunction "CMD_3") (pintype "passive"))
      (node (ref "R21") (pin "2") (pinfunction "2_2") (pintype "passive"))
      (node (ref "R24") (pin "1") (pinfunction "1_1") (pintype "passive"))
    )
    (net (code "29") (name "Net-(J7-CS)") (class "Default")
      (node (ref "J7") (pin "1") (pinfunction "CS_1") (pintype "passive"))
      (node (ref "LCD-MODULE") (pin "21") (pinfunction "LCD_CS_21") (pintype "passive"))
    )
    (net (code "30") (name "Net-(J7-DB0)") (class "Default")
      (node (ref "J7") (pin "6") (pinfunction "DB0_6") (pintype "passive"))
      (node (ref "LCD-MODULE") (pin "18") (pinfunction "DB0_18") (pintype "passive"))
    )
    (net (code "31") (name "Net-(J7-DB1)") (class "Default")
      (node (ref "J7") (pin "7") (pinfunction "DB1_7") (pintype "passive"))
      (node (ref "LCD-MODULE") (pin "17") (pinfunction "DB1_17") (pintype "passive"))
    )
    (net (code "32") (name "Net-(J7-DB2)") (class "Default")
      (node (ref "J7") (pin "8") (pinfunction "DB2_8") (pintype "passive"))
      (node (ref "LCD-MODULE") (pin "16") (pinfunction "DB2_16") (pintype "passive"))
    )
    (net (code "33") (name "Net-(J7-DB3)") (class "Default")
      (node (ref "J7") (pin "9") (pinfunction "DB3_9") (pintype "passive"))
      (node (ref "LCD-MODULE") (pin "15") (pinfunction "DB3_15") (pintype "passive"))
    )
    (net (code "34") (name "Net-(J7-DB4)") (class "Default")
      (node (ref "J7") (pin "10") (pinfunction "DB4_10") (pintype "passive"))
      (node (ref "LCD-MODULE") (pin "14") (pinfunction "DB4_14") (pintype "passive"))
    )
    (net (code "35") (name "Net-(J7-DB5)") (class "Default")
      (node (ref "J7") (pin "11") (pinfunction "DB5_11") (pintype "passive"))
      (node (ref "LCD-MODULE") (pin "13") (pinfunction "DB5_13") (pintype "passive"))
    )
    (net (code "36") (name "Net-(J7-DB6)") (class "Default")
      (node (ref "J7") (pin "12") (pinfunction "DB6_12") (pintype "passive"))
      (node (ref "LCD-MODULE") (pin "12") (pinfunction "DB6_12") (pintype "passive"))
    )
    (net (code "37") (name "Net-(J7-DB7)") (class "Default")
      (node (ref "J7") (pin "13") (pinfunction "DB7_13") (pintype "passive"))
      (node (ref "LCD-MODULE") (pin "11") (pinfunction "DB7_11") (pintype "passive"))
    )
    (net (code "38") (name "Net-(J7-DB8)") (class "Default")
      (node (ref "J7") (pin "14") (pinfunction "DB8_14") (pintype "passive"))
      (node (ref "LCD-MODULE") (pin "3") (pinfunction "DB8_3") (pintype "passive"))
    )
    (net (code "39") (name "Net-(J7-DB9)") (class "Default")
      (node (ref "J7") (pin "15") (pinfunction "DB9_15") (pintype "passive"))
      (node (ref "LCD-MODULE") (pin "4") (pinfunction "DB9_4") (pintype "passive"))
    )
    (net (code "40") (name "Net-(J7-DB10)") (class "Default")
      (node (ref "J7") (pin "16") (pinfunction "DB10_16") (pintype "passive"))
      (node (ref "LCD-MODULE") (pin "5") (pinfunction "DB10_5") (pintype "passive"))
    )
    (net (code "41") (name "Net-(J7-DB11)") (class "Default")
      (node (ref "J7") (pin "17") (pinfunction "DB11_17") (pintype "passive"))
      (node (ref "LCD-MODULE") (pin "6") (pinfunction "DB11_6") (pintype "passive"))
    )
    (net (code "42") (name "Net-(J7-DB12)") (class "Default")
      (node (ref "J7") (pin "18") (pinfunction "DB12_18") (pintype "passive"))
      (node (ref "LCD-MODULE") (pin "7") (pinfunction "DB12_7") (pintype "passive"))
    )
    (net (code "43") (name "Net-(J7-DB13)") (class "Default")
      (node (ref "J7") (pin "19") (pinfunction "DB13_19") (pintype "passive"))
      (node (ref "LCD-MODULE") (pin "8") (pinfunction "DB13_8") (pintype "passive"))
    )
    (net (code "44") (name "Net-(J7-DB14)") (class "Default")
      (node (ref "J7") (pin "20") (pinfunction "DB14_20") (pintype "passive"))
      (node (ref "LCD-MODULE") (pin "9") (pinfunction "DB14_9") (pintype "passive"))
    )
    (net (code "45") (name "Net-(J7-DB15)") (class "Default")
      (node (ref "J7") (pin "21") (pinfunction "DB15_21") (pintype "passive"))
      (node (ref "LCD-MODULE") (pin "10") (pinfunction "DB15_10") (pintype "passive"))
    )
    (net (code "46") (name "Net-(J7-RD)") (class "Default")
      (node (ref "J7") (pin "4") (pinfunction "RD_4") (pintype "passive"))
      (node (ref "LCD-MODULE") (pin "26") (pinfunction "LCD_RD_26") (pintype "passive"))
    )
    (net (code "47") (name "Net-(J7-RS)") (class "Default")
      (node (ref "J7") (pin "2") (pinfunction "RS_2") (pintype "passive"))
      (node (ref "LCD-MODULE") (pin "19") (pinfunction "LCD_RS_19") (pintype "passive"))
    )
    (net (code "48") (name "Net-(J7-RST)") (class "Default")
      (node (ref "J7") (pin "5") (pinfunction "RST_5") (pintype "passive"))
      (node (ref "LCD-MODULE") (pin "22") (pinfunction "LCD_RST_22") (pintype "passive"))
    )
    (net (code "49") (name "Net-(J7-WR)") (class "Default")
      (node (ref "J7") (pin "3") (pinfunction "WR_3") (pintype "passive"))
      (node (ref "LCD-MODULE") (pin "20") (pinfunction "LCD_WR_20") (pintype "passive"))
    )
    (net (code "50") (name "Net-(MOTHERBOARD-1)") (class "Default")
      (node (ref "F2") (pin "2") (pinfunction "2_2") (pintype "passive"))
      (node (ref "MOTHERBOARD") (pin "2") (pinfunction "1_2") (pintype "passive"))
    )
    (net (code "51") (name "Net-(R1-W)") (class "Default")
      (node (ref "R1") (pin "2") (pinfunction "W_2") (pintype "passive"))
      (node (ref "U2") (pin "7") (pinfunction "CH6_7") (pintype "passive"))
    )
    (net (code "52") (name "Net-(R2-W)") (class "Default")
      (node (ref "R2") (pin "2") (pinfunction "W_2") (pintype "passive"))
      (node (ref "U2") (pin "8") (pinfunction "CH7_8") (pintype "passive"))
    )
    (net (code "53") (name "Net-(U1-CH0)") (class "Default")
      (node (ref "R9") (pin "1") (pinfunction "1_1") (pintype "passive"))
      (node (ref "S8") (pin "1") (pinfunction "A_1") (pintype "passive"))
      (node (ref "S8") (pin "2") (pinfunction "A_2") (pintype "passive"))
      (node (ref "U1") (pin "1") (pinfunction "CH0_1") (pintype "passive"))
    )
    (net (code "54") (name "Net-(U1-CH1)") (class "Default")
      (node (ref "R10") (pin "1") (pinfunction "1_1") (pintype "passive"))
      (node (ref "S7") (pin "1") (pinfunction "A_1") (pintype "passive"))
      (node (ref "S7") (pin "2") (pinfunction "A_2") (pintype "passive"))
      (node (ref "U1") (pin "2") (pinfunction "CH1_2") (pintype "passive"))
    )
    (net (code "55") (name "Net-(U1-CH2)") (class "Default")
      (node (ref "R8") (pin "1") (pinfunction "1_1") (pintype "passive"))
      (node (ref "S6") (pin "1") (pinfunction "A_1") (pintype "passive"))
      (node (ref "S6") (pin "2") (pinfunction "A_2") (pintype "passive"))
      (node (ref "U1") (pin "3") (pinfunction "CH2_3") (pintype "passive"))
    )
    (net (code "56") (name "Net-(U1-CH3)") (class "Default")
      (node (ref "R7") (pin "1") (pinfunction "1_1") (pintype "passive"))
      (node (ref "S5") (pin "1") (pinfunction "A_1") (pintype "passive"))
      (node (ref "S5") (pin "2") (pinfunction "A_2") (pintype "passive"))
      (node (ref "U1") (pin "4") (pinfunction "CH3_4") (pintype "passive"))
    )
    (net (code "57") (name "Net-(U1-CH4)") (class "Default")
      (node (ref "R6") (pin "1") (pinfunction "1_1") (pintype "passive"))
      (node (ref "S4") (pin "1") (pinfunction "A_1") (pintype "passive"))
      (node (ref "S4") (pin "2") (pinfunction "A_2") (pintype "passive"))
      (node (ref "U1") (pin "5") (pinfunction "CH4_5") (pintype "passive"))
    )
    (net (code "58") (name "Net-(U1-CH5)") (class "Default")
      (node (ref "R5") (pin "1") (pinfunction "1_1") (pintype "passive"))
      (node (ref "S3") (pin "1") (pinfunction "A_1") (pintype "passive"))
      (node (ref "S3") (pin "2") (pinfunction "A_2") (pintype "passive"))
      (node (ref "U1") (pin "6") (pinfunction "CH5_6") (pintype "passive"))
    )
    (net (code "59") (name "Net-(U1-CH6)") (class "Default")
      (node (ref "R4") (pin "1") (pinfunction "1_1") (pintype "passive"))
      (node (ref "S2") (pin "1") (pinfunction "A_1") (pintype "passive"))
      (node (ref "S2") (pin "2") (pinfunction "A_2") (pintype "passive"))
      (node (ref "U1") (pin "7") (pinfunction "CH6_7") (pintype "passive"))
    )
    (net (code "60") (name "Net-(U1-CH7)") (class "Default")
      (node (ref "R3") (pin "1") (pinfunction "1_1") (pintype "passive"))
      (node (ref "S1") (pin "1") (pinfunction "A_1") (pintype "passive"))
      (node (ref "S1") (pin "2") (pinfunction "A_2") (pintype "passive"))
      (node (ref "U1") (pin "8") (pinfunction "CH7_8") (pintype "passive"))
    )
    (net (code "61") (name "Net-(U2-CH0)") (class "Default")
      (node (ref "R16") (pin "1") (pinfunction "1_1") (pintype "passive"))
      (node (ref "S14") (pin "1") (pinfunction "A_1") (pintype "passive"))
      (node (ref "S14") (pin "2") (pinfunction "A_2") (pintype "passive"))
      (node (ref "U2") (pin "1") (pinfunction "CH0_1") (pintype "passive"))
    )
    (net (code "62") (name "Net-(U2-CH1)") (class "Default")
      (node (ref "R15") (pin "1") (pinfunction "1_1") (pintype "passive"))
      (node (ref "S13") (pin "1") (pinfunction "A_1") (pintype "passive"))
      (node (ref "S13") (pin "2") (pinfunction "A_2") (pintype "passive"))
      (node (ref "U2") (pin "2") (pinfunction "CH1_2") (pintype "passive"))
    )
    (net (code "63") (name "Net-(U2-CH2)") (class "Default")
      (node (ref "R14") (pin "1") (pinfunction "1_1") (pintype "passive"))
      (node (ref "S12") (pin "1") (pinfunction "A_1") (pintype "passive"))
      (node (ref "S12") (pin "2") (pinfunction "A_2") (pintype "passive"))
      (node (ref "U2") (pin "3") (pinfunction "CH2_3") (pintype "passive"))
    )
    (net (code "64") (name "Net-(U2-CH3)") (class "Default")
      (node (ref "R13") (pin "1") (pinfunction "1_1") (pintype "passive"))
      (node (ref "S11") (pin "1") (pinfunction "A_1") (pintype "passive"))
      (node (ref "S11") (pin "2") (pinfunction "A_2") (pintype "passive"))
      (node (ref "U2") (pin "4") (pinfunction "CH3_4") (pintype "passive"))
    )
    (net (code "65") (name "Net-(U2-CH4)") (class "Default")
      (node (ref "R12") (pin "1") (pinfunction "1_1") (pintype "passive"))
      (node (ref "S10") (pin "1") (pinfunction "A_1") (pintype "passive"))
      (node (ref "S10") (pin "2") (pinfunction "A_2") (pintype "passive"))
      (node (ref "U2") (pin "5") (pinfunction "CH4_5") (pintype "passive"))
    )
    (net (code "66") (name "Net-(U2-CH5)") (class "Default")
      (node (ref "R11") (pin "1") (pinfunction "1_1") (pintype "passive"))
      (node (ref "S9") (pin "1") (pinfunction "A_1") (pintype "passive"))
      (node (ref "S9") (pin "2") (pinfunction "A_2") (pintype "passive"))
      (node (ref "U2") (pin "6") (pinfunction "CH5_6") (pintype "passive"))
    )
    (net (code "67") (name "Net-(U3-CH0)") (class "Default")
      (node (ref "R29") (pin "1") (pinfunction "1_1") (pintype "passive"))
      (node (ref "S23") (pin "1") (pinfunction "A_1") (pintype "passive"))
      (node (ref "S23") (pin "2") (pinfunction "A_2") (pintype "passive"))
      (node (ref "U3") (pin "1") (pinfunction "CH0_1") (pintype "passive"))
    )
    (net (code "68") (name "Net-(U3-CH1)") (class "Default")
      (node (ref "R30") (pin "1") (pinfunction "1_1") (pintype "passive"))
      (node (ref "S22") (pin "1") (pinfunction "A_1") (pintype "passive"))
      (node (ref "S22") (pin "2") (pinfunction "A_2") (pintype "passive"))
      (node (ref "U3") (pin "2") (pinfunction "CH1_2") (pintype "passive"))
    )
    (net (code "69") (name "Net-(U3-CH2)") (class "Default")
      (node (ref "R31") (pin "1") (pinfunction "1_1") (pintype "passive"))
      (node (ref "S21") (pin "1") (pinfunction "A_1") (pintype "passive"))
      (node (ref "S21") (pin "2") (pinfunction "A_2") (pintype "passive"))
      (node (ref "U3") (pin "3") (pinfunction "CH2_3") (pintype "passive"))
    )
    (net (code "70") (name "Net-(U3-CH3)") (class "Default")
      (node (ref "R32") (pin "1") (pinfunction "1_1") (pintype "passive"))
      (node (ref "S20") (pin "1") (pinfunction "A_1") (pintype "passive"))
      (node (ref "S20") (pin "2") (pinfunction "A_2") (pintype "passive"))
      (node (ref "U3") (pin "4") (pinfunction "CH3_4") (pintype "passive"))
    )
    (net (code "71") (name "Net-(U3-CH4)") (class "Default")
      (node (ref "R33") (pin "1") (pinfunction "1_1") (pintype "passive"))
      (node (ref "S19") (pin "1") (pinfunction "A_1") (pintype "passive"))
      (node (ref "S19") (pin "2") (pinfunction "A_2") (pintype "passive"))
      (node (ref "U3") (pin "5") (pinfunction "CH4_5") (pintype "passive"))
    )
    (net (code "72") (name "Net-(U3-CH5)") (class "Default")
      (node (ref "R34") (pin "1") (pinfunction "1_1") (pintype "passive"))
      (node (ref "S18") (pin "1") (pinfunction "A_1") (pintype "passive"))
      (node (ref "S18") (pin "2") (pinfunction "A_2") (pintype "passive"))
      (node (ref "U3") (pin "6") (pinfunction "CH5_6") (pintype "passive"))
    )
    (net (code "73") (name "Net-(U3-CH6)") (class "Default")
      (node (ref "R35") (pin "1") (pinfunction "1_1") (pintype "passive"))
      (node (ref "S17") (pin "1") (pinfunction "A_1") (pintype "passive"))
      (node (ref "S17") (pin "2") (pinfunction "A_2") (pintype "passive"))
      (node (ref "U3") (pin "7") (pinfunction "CH6_7") (pintype "passive"))
    )
    (net (code "74") (name "Net-(U3-CH7)") (class "Default")
      (node (ref "R36") (pin "1") (pinfunction "1_1") (pintype "passive"))
      (node (ref "S16") (pin "1") (pinfunction "A_1") (pintype "passive"))
      (node (ref "S16") (pin "2") (pinfunction "A_2") (pintype "passive"))
      (node (ref "U3") (pin "8") (pinfunction "CH7_8") (pintype "passive"))
    )
    (net (code "75") (name "VCC12_IN") (class "Default")
      (node (ref "ACCUM") (pin "2") (pinfunction "1_2") (pintype "passive"))
      (node (ref "Q1") (pin "3") (pinfunction "S_3") (pintype "passive"))
      (node (ref "R26") (pin "2") (pinfunction "2_2") (pintype "passive"))
      (node (ref "R27") (pin "2") (pinfunction "2_2") (pintype "passive"))
      (node (ref "T1") (pin "LCP") (pinfunction "P2_LCP") (pintype "passive"))
    )
    (net (code "76") (name "unconnected-(ESP-8266-GPIO0-Pad3)") (class "Default")
      (node (ref "ESP-8266") (pin "3") (pinfunction "GPIO0_3") (pintype "passive"))
    )
    (net (code "77") (name "unconnected-(ESP-8266-GPIO2-Pad2)") (class "Default")
      (node (ref "ESP-8266") (pin "2") (pinfunction "GPIO2_2") (pintype "passive"))
    )
    (net (code "78") (name "unconnected-(ESP-8266-GPIO16-Pad7)") (class "Default")
      (node (ref "ESP-8266") (pin "7") (pinfunction "GPIO16_7") (pintype "passive"))
    )
    (net (code "79") (name "unconnected-(J2-DAT1-Pad8)") (class "Default")
      (node (ref "J2") (pin "8") (pinfunction "DAT1_8") (pintype "passive"))
    )
    (net (code "80") (name "unconnected-(J2-DAT2-Pad1)") (class "Default")
      (node (ref "J2") (pin "1") (pinfunction "DAT2_1") (pintype "passive"))
    )
    (net (code "81") (name "unconnected-(LCD-MODULE-NC-Pad23)") (class "Default")
      (node (ref "LCD-MODULE") (pin "23") (pinfunction "NC_23") (pintype "passive"))
    )
    (net (code "82") (name "unconnected-(LCD-MODULE-NC-Pad24)") (class "Default")
      (node (ref "LCD-MODULE") (pin "24") (pinfunction "NC_24") (pintype "passive"))
    )
    (net (code "83") (name "unconnected-(LCD-MODULE-NC-Pad25)") (class "Default")
      (node (ref "LCD-MODULE") (pin "25") (pinfunction "NC_25") (pintype "passive"))
    )
    (net (code "84") (name "unconnected-(LCD-MODULE-NC-Pad27)") (class "Default")
      (node (ref "LCD-MODULE") (pin "27") (pinfunction "NC_27") (pintype "passive"))
    )
    (net (code "85") (name "unconnected-(LCD-MODULE-NC-Pad28)") (class "Default")
      (node (ref "LCD-MODULE") (pin "28") (pinfunction "NC_28") (pintype "passive"))
    )
    (net (code "86") (name "unconnected-(LCD-MODULE-NC-Pad29)") (class "Default")
      (node (ref "LCD-MODULE") (pin "29") (pinfunction "NC_29") (pintype "passive"))
    )
    (net (code "87") (name "unconnected-(LCD-MODULE-NC-Pad30)") (class "Default")
      (node (ref "LCD-MODULE") (pin "30") (pinfunction "NC_30") (pintype "passive"))
    )
    (net (code "88") (name "unconnected-(LCD-MODULE-RESET-Pad37)") (class "Default")
      (node (ref "LCD-MODULE") (pin "37") (pinfunction "RESET_37") (pintype "passive"))
    )
    (net (code "89") (name "unconnected-(LCD-MODULE-SD_CLK-Pad33)") (class "Default")
      (node (ref "LCD-MODULE") (pin "33") (pinfunction "SD_CLK_33") (pintype "passive"))
    )
    (net (code "90") (name "unconnected-(LCD-MODULE-SD_CS-Pad34)") (class "Default")
      (node (ref "LCD-MODULE") (pin "34") (pinfunction "SD_CS_34") (pintype "passive"))
    )
    (net (code "91") (name "unconnected-(LCD-MODULE-SD_MISO-Pad31)") (class "Default")
      (node (ref "LCD-MODULE") (pin "31") (pinfunction "SD_MISO_31") (pintype "passive"))
    )
    (net (code "92") (name "unconnected-(LCD-MODULE-SD_MOSI-Pad32)") (class "Default")
      (node (ref "LCD-MODULE") (pin "32") (pinfunction "SD_MOSI_32") (pintype "passive"))
    )
    (net (code "93") (name "unconnected-(M1-ADC-Pad2)") (class "Default")
      (node (ref "M1") (pin "2") (pinfunction "ADC_2") (pintype "passive"))
    )
    (net (code "94") (name "unconnected-(M1-GPIO0-Pad12)") (class "Default")
      (node (ref "M1") (pin "12") (pinfunction "GPIO0_12") (pintype "passive"))
    )
    (net (code "95") (name "unconnected-(M1-GPIO2-Pad11)") (class "Default")
      (node (ref "M1") (pin "11") (pinfunction "GPIO2_11") (pintype "passive"))
    )
    (net (code "96") (name "unconnected-(M1-GPIO4-Pad13)") (class "Default")
      (node (ref "M1") (pin "13") (pinfunction "GPIO4_13") (pintype "passive"))
    )
    (net (code "97") (name "unconnected-(M1-GPIO5-Pad14)") (class "Default")
      (node (ref "M1") (pin "14") (pinfunction "GPIO5_14") (pintype "passive"))
    )
    (net (code "98") (name "unconnected-(M1-GPIO12-Pad6)") (class "Default")
      (node (ref "M1") (pin "6") (pinfunction "GPIO12_6") (pintype "passive"))
    )
    (net (code "99") (name "unconnected-(M1-GPIO13-Pad7)") (class "Default")
      (node (ref "M1") (pin "7") (pinfunction "GPIO13_7") (pintype "passive"))
    )
    (net (code "100") (name "unconnected-(M1-GPIO14-Pad5)") (class "Default")
      (node (ref "M1") (pin "5") (pinfunction "GPIO14_5") (pintype "passive"))
    )
    (net (code "101") (name "unconnected-(M1-GPIO16-Pad4)") (class "Default")
      (node (ref "M1") (pin "4") (pinfunction "GPIO16_4") (pintype "passive"))
    )
    (net (code "102") (name "unconnected-(M1-RST-Pad1)") (class "Default")
      (node (ref "M1") (pin "1") (pinfunction "RST_1") (pintype "passive"))
    )
  )
)
